# PWM_cylinder.net
KiCad netlist of a schematic drawn in Altium Designer
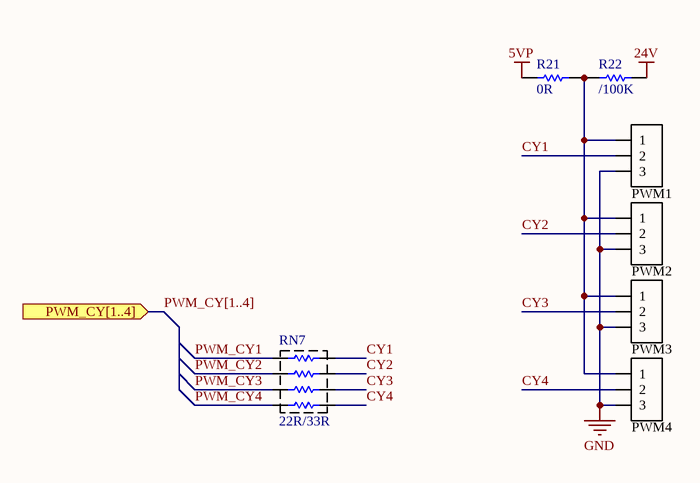
[diagram p0: PWM_cylinder.SchDoc]

(export (version "E")
  (design (tool "Eeschema 10.0.6"))
  (components
    (comp (ref "PWM1")
      (value "Header")
      (footprint "1x3POS_HEADER")
      (description "Header 3-pin")
      (libsource (lib "IOBoard") (part "Header3P"))
    )
    (comp (ref "PWM2")
      (value "Header")
      (footprint "1x3POS_HEADER")
      (description "Header 3-pin")
      (libsource (lib "IOBoard") (part "Header3P"))
    )
    (comp (ref "PWM3")
      (value "Header")
      (footprint "1x3POS_HEADER")
      (description "Header 3-pin")
      (libsource (lib "IOBoard") (part "Header3P"))
    )
    (comp (ref "PWM4")
      (value "Header")
      (footprint "1x3POS_HEADER")
      (description "Header 3-pin")
      (libsource (lib "IOBoard") (part "Header3P"))
    )
    (comp (ref "R21")
      (value "0R")
      (footprint "RESC1608X55N")
      (description "Resistor")
      (fields (field (name "Comment") "Res1") (field (name "PUBLISHER") "Altium Limited"))
      (libsource (lib "IOBoard_Low") (part "Res1"))
    )
    (comp (ref "R22")
      (value "/100K")
      (footprint "RESC1608X55N")
      (description "Resistor")
      (fields (field (name "Comment") "Res1") (field (name "PUBLISHER") "Altium Limited"))
      (libsource (lib "IOBoard_Low") (part "Res1"))
    )
    (comp (ref "RN7")
      (value "22R/33R")
      (footprint "RESCAXS50P160X320X70-8N")
      (fields (field (name "Comment") "resistor network"))
      (libsource (lib "IOBoard") (part "RES_NET"))
    )
  )
  (nets
    (net (code "1") (name "/CY1") (class "Default")
      (node (ref "PWM1") (pin "2") (pinfunction "2_2") (pintype "passive"))
      (node (ref "RN7") (pin "8") (pinfunction "8_8") (pintype "power_in"))
    )
    (net (code "2") (name "/CY2") (class "Default")
      (node (ref "PWM2") (pin "2") (pinfunction "2_2") (pintype "passive"))
      (node (ref "RN7") (pin "7") (pinfunction "7_7") (pintype "power_in"))
    )
    (net (code "3") (name "/CY3") (class "Default")
      (node (ref "PWM3") (pin "2") (pinfunction "2_2") (pintype "passive"))
      (node (ref "RN7") (pin "6") (pinfunction "6_6") (pintype "power_in"))
    )
    (net (code "4") (name "/CY4") (class "Default")
      (node (ref "PWM4") (pin "2") (pinfunction "2_2") (pintype "passive"))
      (node (ref "RN7") (pin "5") (pinfunction "5_5") (pintype "power_in"))
    )
    (net (code "5") (name "/PWM_CY1") (class "Default")
      (node (ref "RN7") (pin "1") (pinfunction "1_1") (pintype "power_in"))
    )
    (net (code "6") (name "/PWM_CY2") (class "Default")
      (node (ref "RN7") (pin "2") (pinfunction "2_2") (pintype "power_in"))
    )
    (net (code "7") (name "/PWM_CY3") (class "Default")
      (node (ref "RN7") (pin "3") (pinfunction "3_3") (pintype "power_in"))
    )
    (net (code "8") (name "/PWM_CY4") (class "Default")
      (node (ref "RN7") (pin "4") (pinfunction "4_4") (pintype "power_in"))
    )
    (net (code "10") (name "5VP") (class "Default")
      (node (ref "R21") (pin "2") (pinfunction "2_2") (pintype "passive"))
    )
    (net (code "11") (name "24V") (class "Default")
      (node (ref "R22") (pin "1") (pinfunction "1_1") (pintype "passive"))
    )
    (net (code "12") (name "GND") (class "Default")
      (node (ref "PWM1") (pin "3") (pinfunction "3_3") (pintype "passive"))
      (node (ref "PWM2") (pin "3") (pinfunction "3_3") (pintype "passive"))
      (node (ref "PWM3") (pin "3") (pinfunction "3_3") (pintype "passive"))
      (node (ref "PWM4") (pin "3") (pinfunction "3_3") (pintype "passive"))
    )
    (net (code "13") (name "Net-(PWM1-Pad1)") (class "Default")
      (node (ref "PWM1") (pin "1") (pinfunction "1_1") (pintype "passive"))
      (node (ref "PWM2") (pin "1") (pinfunction "1_1") (pintype "passive"))
      (node (ref "PWM3") (pin "1") (pinfunction "1_1") (pintype "passive"))
      (node (ref "PWM4") (pin "1") (pinfunction "1_1") (pintype "passive"))
      (node (ref "R21") (pin "1") (pinfunction "1_1") (pintype "passive"))
      (node (ref "R22") (pin "2") (pinfunction "2_2") (pintype "passive"))
    )
  )
)
